# transmitter_150Mhz.net
KiCad netlist of a schematic drawn in EAGLE
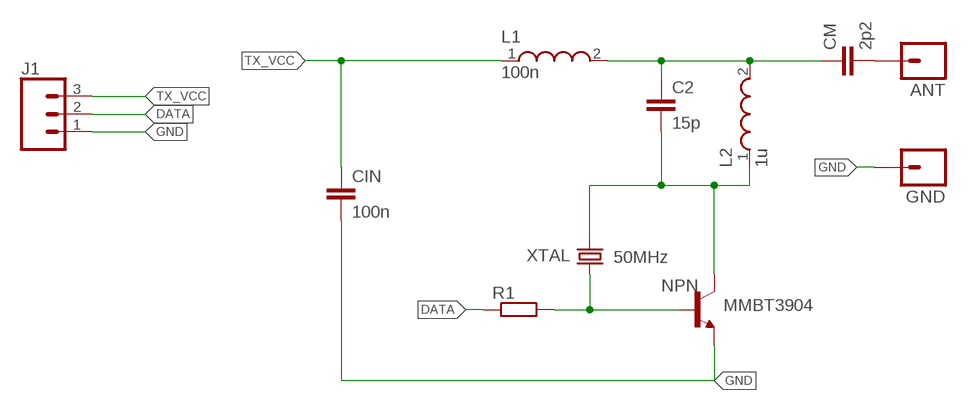
[diagram p0: schematic, sheet 1]

(export (version "E")
  (design (tool "Eeschema 10.0.6"))
  (components
    (comp (ref "ANT")
      (value "M01OFFSET")
      (footprint "eagle-import:1X01_OFFSET")
      (libsource (lib "eagle-import") (part "M01OFFSET"))
    )
    (comp (ref "C2")
      (value "15p")
      (footprint "eagle-import:C0603")
      (libsource (lib "eagle-import") (part "C-EUC0603"))
    )
    (comp (ref "CIN")
      (value "100n")
      (footprint "eagle-import:C0603")
      (libsource (lib "eagle-import") (part "C-EUC0603"))
    )
    (comp (ref "CM")
      (value "2p2")
      (footprint "eagle-import:C0603")
      (libsource (lib "eagle-import") (part "C-EUC0603"))
    )
    (comp (ref "GND")
      (value "M01OFFSET")
      (footprint "eagle-import:1X01_OFFSET")
      (libsource (lib "eagle-import") (part "M01OFFSET"))
    )
    (comp (ref "J1")
      (value "CONN_03")
      (footprint "eagle-import:1X03")
      (libsource (lib "eagle-import") (part "CONN_03"))
    )
    (comp (ref "L1")
      (value "100n")
      (footprint "eagle-import:WE-PMI_0805")
      (libsource (lib "eagle-import") (part "WE-PMI_0805"))
    )
    (comp (ref "L2")
      (value "1u")
      (footprint "eagle-import:WE-PMI_0806")
      (libsource (lib "eagle-import") (part "WE-PMI_0806"))
    )
    (comp (ref "NPN")
      (value "MMBT3904")
      (footprint "eagle-import:SOT23-BEC")
      (libsource (lib "eagle-import") (part "-NPN-SOT23-BECMMBT3904LT1"))
    )
    (comp (ref "R1")
      (value "R-EU_R0603")
      (footprint "eagle-import:R0603")
      (libsource (lib "eagle-import") (part "R-EU_R0603"))
    )
    (comp (ref "XTAL")
      (value "50MHz")
      (footprint "eagle-import:SM49")
      (libsource (lib "eagle-import") (part "CRYSTALSM49"))
    )
  )
  (nets
    (net (code "1") (name "DATA") (class "Default")
      (node (ref "J1") (pin "2") (pinfunction "2_2") (pintype "passive"))
      (node (ref "R1") (pin "1") (pinfunction "1_1") (pintype "passive"))
    )
    (net (code "2") (name "GND") (class "Default")
      (node (ref "CIN") (pin "2") (pinfunction "2_2") (pintype "passive"))
      (node (ref "GND") (pin "1") (pinfunction "1_1") (pintype "passive"))
      (node (ref "J1") (pin "1") (pinfunction "1_1") (pintype "passive"))
      (node (ref "NPN") (pin "E") (pinfunction "E_E") (pintype "passive"))
    )
    (net (code "3") (name "Net-(ANT-Pad1)") (class "Default")
      (node (ref "ANT") (pin "1") (pinfunction "1_1") (pintype "passive"))
      (node (ref "CM") (pin "2") (pinfunction "2_2") (pintype "passive"))
    )
    (net (code "4") (name "Net-(C2-Pad1)") (class "Default")
      (node (ref "C2") (pin "1") (pinfunction "1_1") (pintype "passive"))
      (node (ref "CM") (pin "1") (pinfunction "1_1") (pintype "passive"))
      (node (ref "L1") (pin "2") (pinfunction "2_2") (pintype "passive"))
      (node (ref "L2") (pin "2") (pinfunction "2_2") (pintype "passive"))
    )
    (net (code "5") (name "Net-(C2-Pad2)") (class "Default")
      (node (ref "C2") (pin "2") (pinfunction "2_2") (pintype "passive"))
      (node (ref "L2") (pin "1") (pinfunction "1_1") (pintype "passive"))
      (node (ref "NPN") (pin "C") (pinfunction "C_C") (pintype "passive"))
      (node (ref "XTAL") (pin "2") (pinfunction "2_2") (pintype "passive"))
    )
    (net (code "6") (name "Net-(NPN-PadB)") (class "Default")
      (node (ref "NPN") (pin "B") (pinfunction "B_B") (pintype "passive"))
      (node (ref "R1") (pin "2") (pinfunction "2_2") (pintype "passive"))
      (node (ref "XTAL") (pin "1") (pinfunction "1_1") (pintype "passive"))
    )
    (net (code "7") (name "TX_VCC") (class "Default")
      (node (ref "CIN") (pin "1") (pinfunction "1_1") (pintype "passive"))
      (node (ref "J1") (pin "3") (pinfunction "3_3") (pintype "passive"))
      (node (ref "L1") (pin "1") (pinfunction "1_1") (pintype "passive"))
    )
  )
)
